# Power_ab.net
KiCad netlist of a schematic drawn in EAGLE
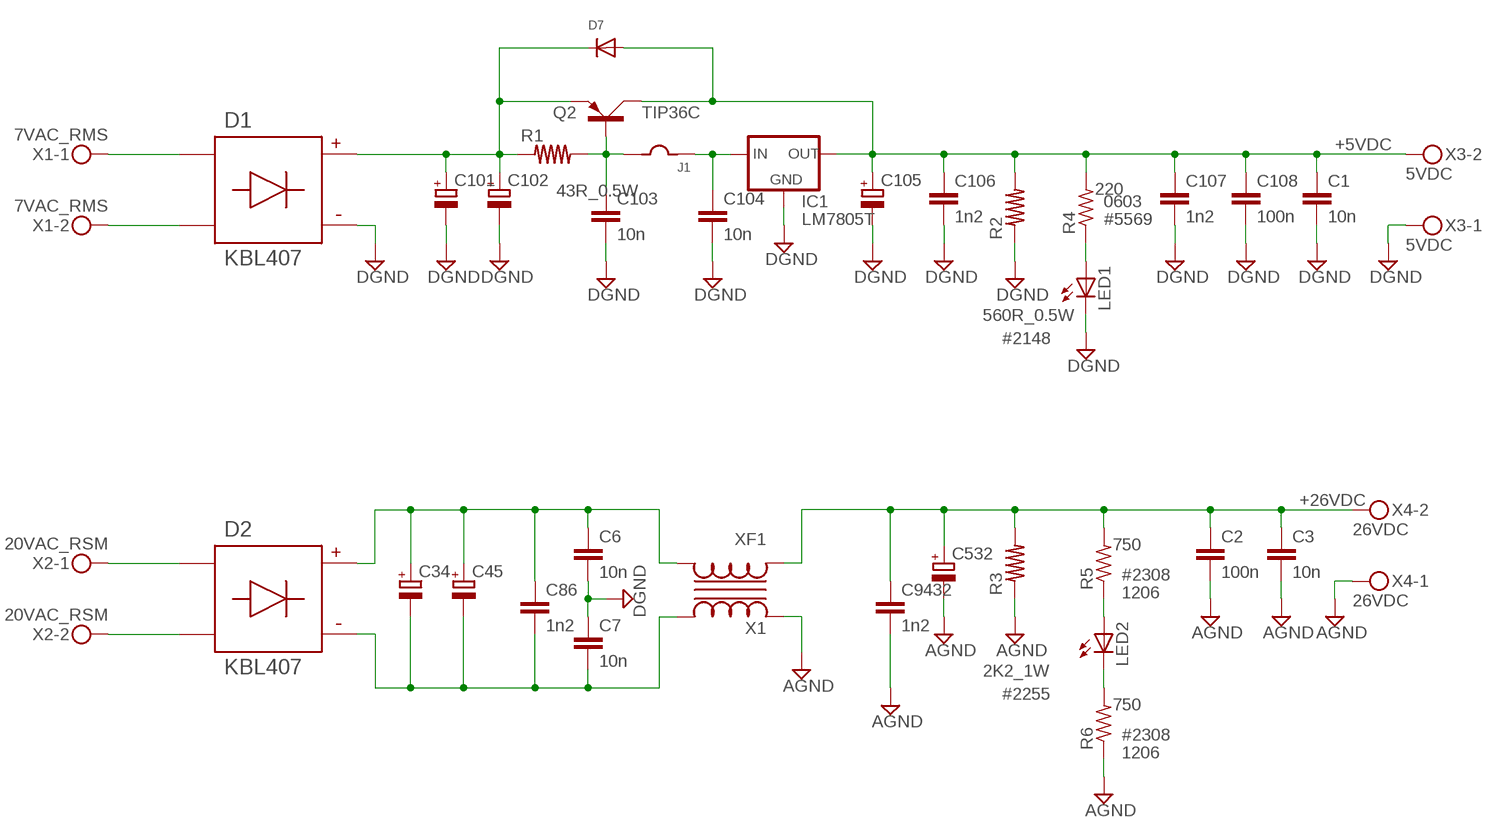
[diagram p0: schematic, sheet 1]

(export (version "E")
  (design (tool "Eeschema 10.0.6"))
  (components
    (comp (ref "C1")
      (value "10n")
      (footprint "eagle-import:C1206")
      (libsource (lib "eagle-import") (part "C-EUC1206"))
    )
    (comp (ref "C2")
      (value "100n")
      (footprint "eagle-import:C1206")
      (libsource (lib "eagle-import") (part "C-EUC1206"))
    )
    (comp (ref "C3")
      (value "10n")
      (footprint "eagle-import:C1206")
      (libsource (lib "eagle-import") (part "C-EUC1206"))
    )
    (comp (ref "C6")
      (value "10n")
      (footprint "eagle-import:C1206")
      (libsource (lib "eagle-import") (part "C-EUC1206"))
    )
    (comp (ref "C7")
      (value "10n")
      (footprint "eagle-import:C1206")
      (libsource (lib "eagle-import") (part "C-EUC1206"))
    )
    (comp (ref "C34")
      (value "CPOL-EUEB20C")
      (footprint "eagle-import:EB20C")
      (libsource (lib "eagle-import") (part "CPOL-EUEB20C"))
    )
    (comp (ref "C45")
      (value "CPOL-EUEB20C")
      (footprint "eagle-import:EB20C")
      (libsource (lib "eagle-import") (part "CPOL-EUEB20C"))
    )
    (comp (ref "C86")
      (value "1n2")
      (footprint "eagle-import:C075-032X103")
      (libsource (lib "eagle-import") (part "C-EU075-032X103"))
    )
    (comp (ref "C101")
      (value "CPOL-EUE7.5-18")
      (footprint "eagle-import:E7,5-18")
      (libsource (lib "eagle-import") (part "CPOL-EUE7.5-18"))
    )
    (comp (ref "C102")
      (value "CPOL-EUE7.5-18")
      (footprint "eagle-import:E7,5-18")
      (libsource (lib "eagle-import") (part "CPOL-EUE7.5-18"))
    )
    (comp (ref "C103")
      (value "10n")
      (footprint "eagle-import:C1206")
      (libsource (lib "eagle-import") (part "C-EUC1206"))
    )
    (comp (ref "C104")
      (value "10n")
      (footprint "eagle-import:C1206")
      (libsource (lib "eagle-import") (part "C-EUC1206"))
    )
    (comp (ref "C105")
      (value "CPOL-EUE7.5-18")
      (footprint "eagle-import:E7,5-18")
      (libsource (lib "eagle-import") (part "CPOL-EUE7.5-18"))
    )
    (comp (ref "C106")
      (value "1n2")
      (footprint "eagle-import:C075-032X103")
      (libsource (lib "eagle-import") (part "C-EU075-032X103"))
    )
    (comp (ref "C107")
      (value "1n2")
      (footprint "eagle-import:C075-032X103")
      (libsource (lib "eagle-import") (part "C-EU075-032X103"))
    )
    (comp (ref "C108")
      (value "100n")
      (footprint "eagle-import:C1206")
      (libsource (lib "eagle-import") (part "C-EUC1206"))
    )
    (comp (ref "C532")
      (value "CPOL-EUEB20C")
      (footprint "eagle-import:EB20C")
      (libsource (lib "eagle-import") (part "CPOL-EUEB20C"))
    )
    (comp (ref "C9432")
      (value "1n2")
      (footprint "eagle-import:C075-032X103")
      (libsource (lib "eagle-import") (part "C-EU075-032X103"))
    )
    (comp (ref "D1")
      (value "KBL407")
      (footprint "eagle-import:KBL")
      (libsource (lib "eagle-import") (part "KBL407"))
    )
    (comp (ref "D2")
      (value "KBL407")
      (footprint "eagle-import:KBL")
      (libsource (lib "eagle-import") (part "KBL407"))
    )
    (comp (ref "D7")
      (value "1N4007")
      (footprint "eagle-import:DO-41")
      (libsource (lib "eagle-import") (part "1N4007"))
    )
    (comp (ref "IC1")
      (value "LM7805T")
      (footprint "eagle-import:78XXS")
      (libsource (lib "eagle-import") (part "78XXS"))
    )
    (comp (ref "J1")
      (value "JUMP350MILS")
      (footprint "eagle-import:JUMP350")
      (libsource (lib "eagle-import") (part "JUMP350MILS"))
    )
    (comp (ref "LED1")
      (value "LED5MM")
      (footprint "eagle-import:LED5MM")
      (libsource (lib "eagle-import") (part "LED5MM"))
    )
    (comp (ref "LED2")
      (value "LED5MM")
      (footprint "eagle-import:LED5MM")
      (libsource (lib "eagle-import") (part "LED5MM"))
    )
    (comp (ref "Q2")
      (value "TIP36C")
      (footprint "eagle-import:TOP3AV")
      (libsource (lib "eagle-import") (part "TIP2955"))
    )
    (comp (ref "R1")
      (value "43R_0.5W")
      (footprint "eagle-import:50R500")
      (libsource (lib "eagle-import") (part "R0W50500MILS"))
    )
    (comp (ref "R2")
      (value "560R_0.5W")
      (footprint "eagle-import:50R500")
      (fields (field (name "ALMACEN") "#2148"))
      (libsource (lib "eagle-import") (part "R0W50500MILS"))
    )
    (comp (ref "R3")
      (value "2K2_1W")
      (footprint "eagle-import:50R500")
      (fields (field (name "ALMACEN") "#2255"))
      (libsource (lib "eagle-import") (part "R0W50500MILS"))
    )
    (comp (ref "R4")
      (value "220")
      (footprint "eagle-import:R0603")
      (fields (field (name "ALMACEN") "#5569") (field (name "PACKAGE") "0603"))
      (libsource (lib "eagle-import") (part "R-US_R0603"))
    )
    (comp (ref "R5")
      (value "750")
      (footprint "eagle-import:R1206")
      (fields (field (name "ALMACEN") "#2308") (field (name "PACKAGE") "1206"))
      (libsource (lib "eagle-import") (part "R-US_R1206"))
    )
    (comp (ref "R6")
      (value "750")
      (footprint "eagle-import:R1206")
      (fields (field (name "ALMACEN") "#2308") (field (name "PACKAGE") "1206"))
      (libsource (lib "eagle-import") (part "R-US_R1206"))
    )
    (comp (ref "X1")
      (value "7VAC_RMS")
      (footprint "eagle-import:MKDSN1,5_2-5,08")
      (libsource (lib "eagle-import") (part "MKDSN1,5/2-5,08"))
    )
    (comp (ref "X2")
      (value "20VAC_RSM")
      (footprint "eagle-import:MKDSN1,5_2-5,08")
      (libsource (lib "eagle-import") (part "MKDSN1,5/2-5,08"))
    )
    (comp (ref "X3")
      (value "5VDC")
      (footprint "eagle-import:MKDSN1,5_2-5,08")
      (libsource (lib "eagle-import") (part "MKDSN1,5/2-5,08"))
    )
    (comp (ref "X4")
      (value "26VDC")
      (footprint "eagle-import:MKDSN1,5_2-5,08")
      (libsource (lib "eagle-import") (part "MKDSN1,5/2-5,08"))
    )
    (comp (ref "XF1")
      (value "X1")
      (footprint "eagle-import:TORO1")
      (libsource (lib "eagle-import") (part "TRF_LINETRF_LINE"))
    )
  )
  (nets
    (net (code "1") (name "/+5VDC") (class "Default")
      (node (ref "C1") (pin "1") (pinfunction "1_1") (pintype "passive"))
      (node (ref "C105") (pin "+") (pinfunction "+_+") (pintype "passive"))
      (node (ref "C106") (pin "1") (pinfunction "1_1") (pintype "passive"))
      (node (ref "C107") (pin "1") (pinfunction "1_1") (pintype "passive"))
      (node (ref "C108") (pin "1") (pinfunction "1_1") (pintype "passive"))
      (node (ref "D7") (pin "A") (pinfunction "ANODE_A") (pintype "bidirectional"))
      (node (ref "IC1") (pin "OUT") (pinfunction "OUT_OUT") (pintype "passive"))
      (node (ref "Q2") (pin "C") (pinfunction "C_C") (pintype "passive"))
      (node (ref "R2") (pin "P$2") (pinfunction "P$2_P$2") (pintype "bidirectional"))
      (node (ref "R4") (pin "2") (pinfunction "2_2") (pintype "passive"))
      (node (ref "X3") (pin "2") (pinfunction "KL_2") (pintype "passive"))
    )
    (net (code "2") (name "/+26VDC") (class "Default")
      (node (ref "C2") (pin "1") (pinfunction "1_1") (pintype "passive"))
      (node (ref "C3") (pin "1") (pinfunction "1_1") (pintype "passive"))
      (node (ref "C532") (pin "+") (pinfunction "+_+") (pintype "passive"))
      (node (ref "C9432") (pin "1") (pinfunction "1_1") (pintype "passive"))
      (node (ref "R3") (pin "P$2") (pinfunction "P$2_P$2") (pintype "bidirectional"))
      (node (ref "R5") (pin "2") (pinfunction "2_2") (pintype "passive"))
      (node (ref "X4") (pin "2") (pinfunction "KL_2") (pintype "passive"))
      (node (ref "XF1") (pin "L1A") (pinfunction "L1A_L1A") (pintype "bidirectional"))
    )
    (net (code "3") (name "AGND") (class "Default")
      (node (ref "C2") (pin "2") (pinfunction "2_2") (pintype "passive"))
      (node (ref "C3") (pin "2") (pinfunction "2_2") (pintype "passive"))
      (node (ref "C532") (pin "-") (pinfunction "-_-") (pintype "passive"))
      (node (ref "C9432") (pin "2") (pinfunction "2_2") (pintype "passive"))
      (node (ref "R3") (pin "P$1") (pinfunction "P$1_P$1") (pintype "bidirectional"))
      (node (ref "R6") (pin "1") (pinfunction "1_1") (pintype "passive"))
      (node (ref "X4") (pin "1") (pinfunction "KL_1") (pintype "passive"))
      (node (ref "XF1") (pin "L2A") (pinfunction "L2A_L2A") (pintype "bidirectional"))
    )
    (net (code "4") (name "DGND") (class "Default")
      (node (ref "C1") (pin "2") (pinfunction "2_2") (pintype "passive"))
      (node (ref "C101") (pin "-") (pinfunction "-_-") (pintype "passive"))
      (node (ref "C102") (pin "-") (pinfunction "-_-") (pintype "passive"))
      (node (ref "C103") (pin "2") (pinfunction "2_2") (pintype "passive"))
      (node (ref "C104") (pin "2") (pinfunction "2_2") (pintype "passive"))
      (node (ref "C105") (pin "-") (pinfunction "-_-") (pintype "passive"))
      (node (ref "C106") (pin "2") (pinfunction "2_2") (pintype "passive"))
      (node (ref "C107") (pin "2") (pinfunction "2_2") (pintype "passive"))
      (node (ref "C108") (pin "2") (pinfunction "2_2") (pintype "passive"))
      (node (ref "C6") (pin "2") (pinfunction "2_2") (pintype "passive"))
      (node (ref "C7") (pin "1") (pinfunction "1_1") (pintype "passive"))
      (node (ref "D1") (pin "-") (pinfunction "-_-") (pintype "bidirectional"))
      (node (ref "IC1") (pin "GND") (pinfunction "GND_GND") (pintype "input"))
      (node (ref "LED1") (pin "K") (pinfunction "C_K") (pintype "passive"))
      (node (ref "R2") (pin "P$1") (pinfunction "P$1_P$1") (pintype "bidirectional"))
      (node (ref "X3") (pin "1") (pinfunction "KL_1") (pintype "passive"))
    )
    (net (code "5") (name "Net-(C34-Pad+)") (class "Default")
      (node (ref "C34") (pin "+") (pinfunction "+_+") (pintype "passive"))
      (node (ref "C45") (pin "+") (pinfunction "+_+") (pintype "passive"))
      (node (ref "C6") (pin "1") (pinfunction "1_1") (pintype "passive"))
      (node (ref "C86") (pin "1") (pinfunction "1_1") (pintype "passive"))
      (node (ref "D2") (pin "+") (pinfunction "+_+") (pintype "bidirectional"))
      (node (ref "XF1") (pin "L1B") (pinfunction "L1B_L1B") (pintype "bidirectional"))
    )
    (net (code "6") (name "Net-(C34-Pad-)") (class "Default")
      (node (ref "C34") (pin "-") (pinfunction "-_-") (pintype "passive"))
      (node (ref "C45") (pin "-") (pinfunction "-_-") (pintype "passive"))
      (node (ref "C7") (pin "2") (pinfunction "2_2") (pintype "passive"))
      (node (ref "C86") (pin "2") (pinfunction "2_2") (pintype "passive"))
      (node (ref "D2") (pin "-") (pinfunction "-_-") (pintype "bidirectional"))
      (node (ref "XF1") (pin "L2B") (pinfunction "L2B_L2B") (pintype "bidirectional"))
    )
    (net (code "7") (name "Net-(C103-Pad1)") (class "Default")
      (node (ref "C103") (pin "1") (pinfunction "1_1") (pintype "passive"))
      (node (ref "J1") (pin "P$1") (pinfunction "P$1_P$1") (pintype "bidirectional"))
      (node (ref "Q2") (pin "B") (pinfunction "B_B") (pintype "passive"))
      (node (ref "R1") (pin "P$2") (pinfunction "P$2_P$2") (pintype "bidirectional"))
    )
    (net (code "8") (name "Net-(C104-Pad1)") (class "Default")
      (node (ref "C104") (pin "1") (pinfunction "1_1") (pintype "passive"))
      (node (ref "IC1") (pin "IN") (pinfunction "IN_IN") (pintype "input"))
      (node (ref "J1") (pin "P$2") (pinfunction "P$2_P$2") (pintype "bidirectional"))
    )
    (net (code "9") (name "Net-(D7-KATODE)") (class "Default")
      (node (ref "C101") (pin "+") (pinfunction "+_+") (pintype "passive"))
      (node (ref "C102") (pin "+") (pinfunction "+_+") (pintype "passive"))
      (node (ref "D1") (pin "+") (pinfunction "+_+") (pintype "bidirectional"))
      (node (ref "D7") (pin "K") (pinfunction "KATODE_K") (pintype "bidirectional"))
      (node (ref "Q2") (pin "E") (pinfunction "E_E") (pintype "passive"))
      (node (ref "R1") (pin "P$1") (pinfunction "P$1_P$1") (pintype "bidirectional"))
    )
    (net (code "10") (name "Net-(LED1-PadA)") (class "Default")
      (node (ref "LED1") (pin "A") (pinfunction "A_A") (pintype "passive"))
      (node (ref "R4") (pin "1") (pinfunction "1_1") (pintype "passive"))
    )
    (net (code "11") (name "Net-(LED2-C)") (class "Default")
      (node (ref "LED2") (pin "K") (pinfunction "C_K") (pintype "passive"))
      (node (ref "R6") (pin "2") (pinfunction "2_2") (pintype "passive"))
    )
    (net (code "12") (name "Net-(LED2-PadA)") (class "Default")
      (node (ref "LED2") (pin "A") (pinfunction "A_A") (pintype "passive"))
      (node (ref "R5") (pin "1") (pinfunction "1_1") (pintype "passive"))
    )
    (net (code "13") (name "Net-(X1A-KL)") (class "Default")
      (node (ref "D1") (pin "AC1") (pinfunction "AC1_AC1") (pintype "input"))
      (node (ref "X1") (pin "1") (pinfunction "KL_1") (pintype "passive"))
    )
    (net (code "14") (name "Net-(X1B-KL)") (class "Default")
      (node (ref "D1") (pin "AC2") (pinfunction "AC2_AC2") (pintype "bidirectional"))
      (node (ref "X1") (pin "2") (pinfunction "KL_2") (pintype "passive"))
    )
    (net (code "15") (name "Net-(X2A-KL)") (class "Default")
      (node (ref "D2") (pin "AC1") (pinfunction "AC1_AC1") (pintype "input"))
      (node (ref "X2") (pin "1") (pinfunction "KL_1") (pintype "passive"))
    )
    (net (code "16") (name "Net-(X2B-KL)") (class "Default")
      (node (ref "D2") (pin "AC2") (pinfunction "AC2_AC2") (pintype "bidirectional"))
      (node (ref "X2") (pin "2") (pinfunction "KL_2") (pintype "passive"))
    )
  )
)
